# nintendac.net
KiCad netlist of a schematic drawn in EAGLE
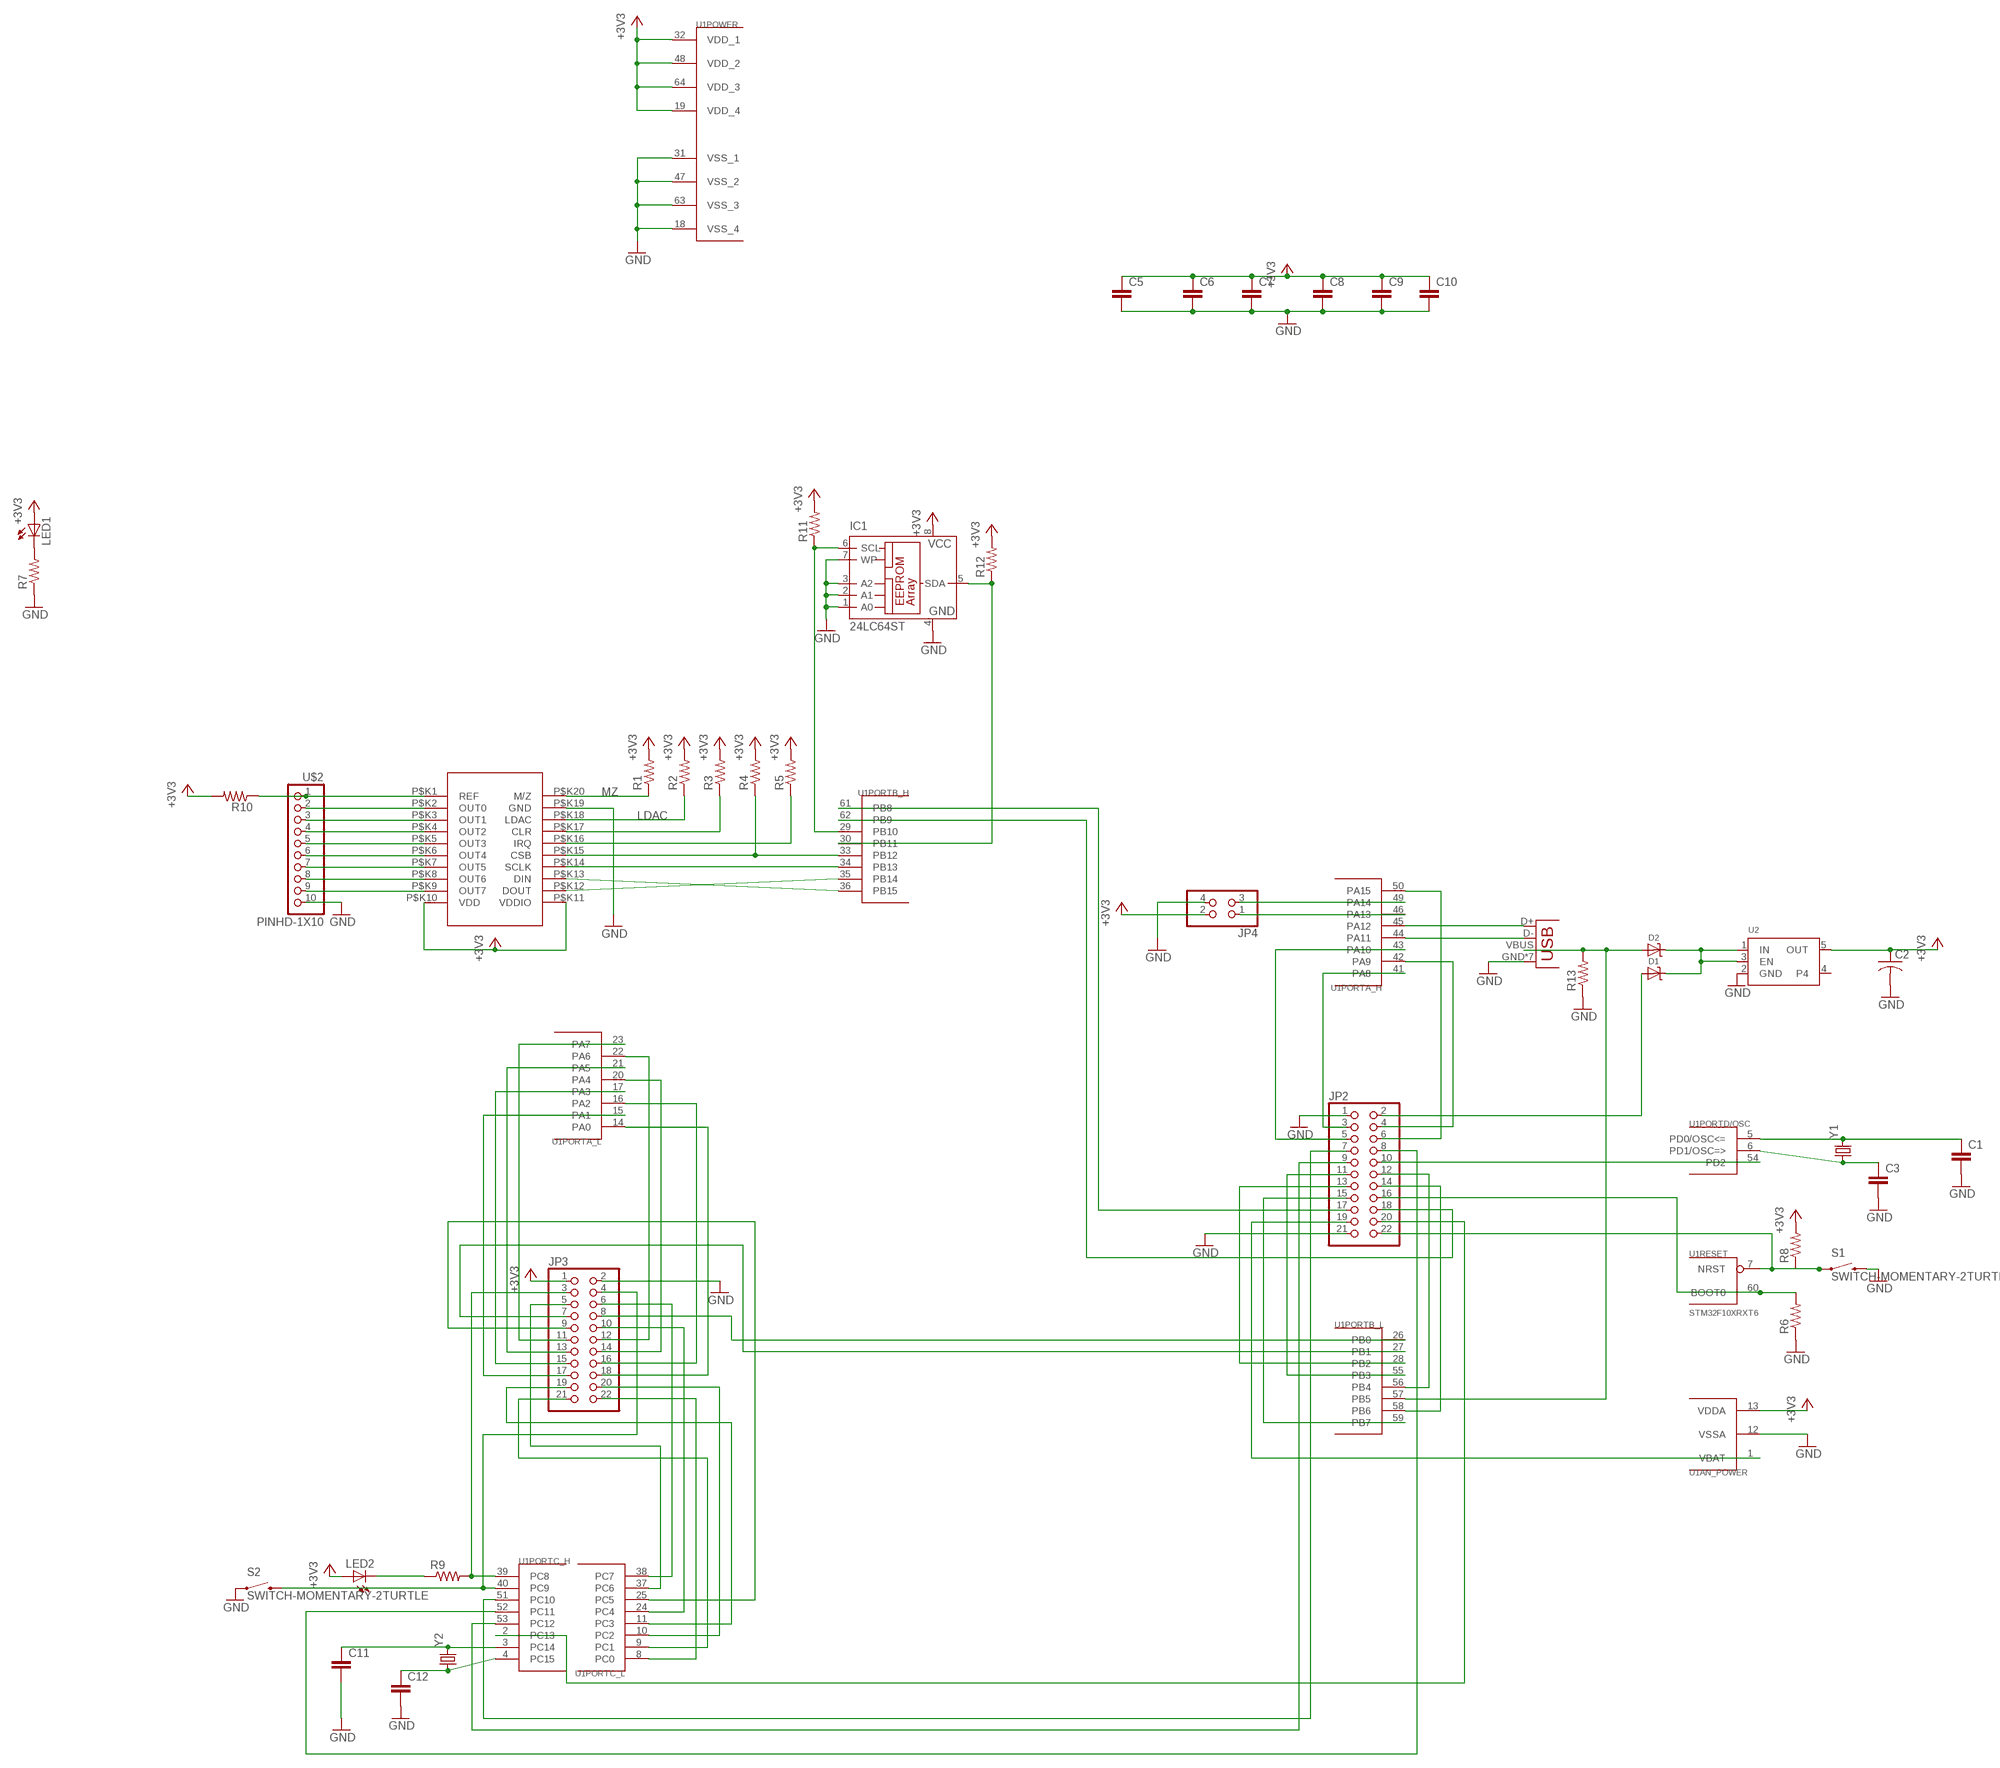
[diagram p0: schematic, sheet 1]

(export (version "E")
  (design (tool "Eeschema 10.0.6"))
  (components
    (comp (ref "C1")
      (value "CAP0805")
      (footprint "eagle-import:0805")
      (libsource (lib "eagle-import") (part "CAP0805"))
    )
    (comp (ref "C2")
      (value "C-USC1210")
      (footprint "eagle-import:C1210")
      (libsource (lib "eagle-import") (part "C-USC1210"))
    )
    (comp (ref "C3")
      (value "CAP0805")
      (footprint "eagle-import:0805")
      (libsource (lib "eagle-import") (part "CAP0805"))
    )
    (comp (ref "C5")
      (value "CAP0805")
      (footprint "eagle-import:0805")
      (libsource (lib "eagle-import") (part "CAP0805"))
    )
    (comp (ref "C6")
      (value "CAP0805")
      (footprint "eagle-import:0805")
      (libsource (lib "eagle-import") (part "CAP0805"))
    )
    (comp (ref "C7")
      (value "CAP0805")
      (footprint "eagle-import:0805")
      (libsource (lib "eagle-import") (part "CAP0805"))
    )
    (comp (ref "C8")
      (value "CAP0805")
      (footprint "eagle-import:0805")
      (libsource (lib "eagle-import") (part "CAP0805"))
    )
    (comp (ref "C9")
      (value "CAP0805")
      (footprint "eagle-import:0805")
      (libsource (lib "eagle-import") (part "CAP0805"))
    )
    (comp (ref "C10")
      (value "CAP0805")
      (footprint "eagle-import:0805")
      (libsource (lib "eagle-import") (part "CAP0805"))
    )
    (comp (ref "C11")
      (value "CAP0805")
      (footprint "eagle-import:0805")
      (libsource (lib "eagle-import") (part "CAP0805"))
    )
    (comp (ref "C12")
      (value "CAP0805")
      (footprint "eagle-import:0805")
      (libsource (lib "eagle-import") (part "CAP0805"))
    )
    (comp (ref "D1")
      (value "DIODE-SCHOTTKYSOD-123")
      (footprint "eagle-import:SOD-123")
      (libsource (lib "eagle-import") (part "DIODE-SCHOTTKYSOD-123"))
    )
    (comp (ref "D2")
      (value "DIODE-SCHOTTKYSOD-123")
      (footprint "eagle-import:SOD-123")
      (libsource (lib "eagle-import") (part "DIODE-SCHOTTKYSOD-123"))
    )
    (comp (ref "IC1")
      (value "24LC64ST")
      (footprint "eagle-import:TSSOP8")
      (fields (field (name "MF") "MICROCHIP") (field (name "MPN") "24LC64X-I/ST"))
      (libsource (lib "eagle-import") (part "24STLC64"))
    )
    (comp (ref "JP2")
      (value "PINHD-2X11")
      (footprint "eagle-import:2X11")
      (libsource (lib "eagle-import") (part "PINHD-2X11"))
    )
    (comp (ref "JP3")
      (value "PINHD-2X11")
      (footprint "eagle-import:2X11")
      (libsource (lib "eagle-import") (part "PINHD-2X11"))
    )
    (comp (ref "JP4")
      (value "PINHD-2X2")
      (footprint "eagle-import:2X02")
      (libsource (lib "eagle-import") (part "PINHD-2X2"))
    )
    (comp (ref "LED1")
      (value "LEDCHIP-LED0805")
      (footprint "eagle-import:CHIP-LED0805")
      (libsource (lib "eagle-import") (part "LEDCHIP-LED0805"))
    )
    (comp (ref "LED2")
      (value "LEDCHIP-LED0805")
      (footprint "eagle-import:CHIP-LED0805")
      (libsource (lib "eagle-import") (part "LEDCHIP-LED0805"))
    )
    (comp (ref "R1")
      (value "RESISTOR0805-RES")
      (footprint "eagle-import:0805")
      (libsource (lib "eagle-import") (part "RESISTOR0805-RES"))
    )
    (comp (ref "R2")
      (value "RESISTOR0805-RES")
      (footprint "eagle-import:0805")
      (libsource (lib "eagle-import") (part "RESISTOR0805-RES"))
    )
    (comp (ref "R3")
      (value "RESISTOR0805-RES")
      (footprint "eagle-import:0805")
      (libsource (lib "eagle-import") (part "RESISTOR0805-RES"))
    )
    (comp (ref "R4")
      (value "RESISTOR0805-RES")
      (footprint "eagle-import:0805")
      (libsource (lib "eagle-import") (part "RESISTOR0805-RES"))
    )
    (comp (ref "R5")
      (value "RESISTOR0805-RES")
      (footprint "eagle-import:0805")
      (libsource (lib "eagle-import") (part "RESISTOR0805-RES"))
    )
    (comp (ref "R6")
      (value "RESISTOR0805-RES")
      (footprint "eagle-import:0805")
      (libsource (lib "eagle-import") (part "RESISTOR0805-RES"))
    )
    (comp (ref "R7")
      (value "RESISTOR0805-RES")
      (footprint "eagle-import:0805")
      (libsource (lib "eagle-import") (part "RESISTOR0805-RES"))
    )
    (comp (ref "R8")
      (value "RESISTOR0805-RES")
      (footprint "eagle-import:0805")
      (libsource (lib "eagle-import") (part "RESISTOR0805-RES"))
    )
    (comp (ref "R9")
      (value "RESISTOR0805-RES")
      (footprint "eagle-import:0805")
      (libsource (lib "eagle-import") (part "RESISTOR0805-RES"))
    )
    (comp (ref "R10")
      (value "RESISTOR0805-RES")
      (footprint "eagle-import:0805")
      (libsource (lib "eagle-import") (part "RESISTOR0805-RES"))
    )
    (comp (ref "R11")
      (value "RESISTOR0805-RES")
      (footprint "eagle-import:0805")
      (libsource (lib "eagle-import") (part "RESISTOR0805-RES"))
    )
    (comp (ref "R12")
      (value "RESISTOR0805-RES")
      (footprint "eagle-import:0805")
      (libsource (lib "eagle-import") (part "RESISTOR0805-RES"))
    )
    (comp (ref "R13")
      (value "RESISTOR0805-RES")
      (footprint "eagle-import:0805")
      (libsource (lib "eagle-import") (part "RESISTOR0805-RES"))
    )
    (comp (ref "S1")
      (value "SWITCH-MOMENTARY-2TURTLE")
      (footprint "eagle-import:KMR2")
      (libsource (lib "eagle-import") (part "SWITCH-MOMENTARY-2TURTLE"))
    )
    (comp (ref "S2")
      (value "SWITCH-MOMENTARY-2TURTLE")
      (footprint "eagle-import:KMR2")
      (libsource (lib "eagle-import") (part "SWITCH-MOMENTARY-2TURTLE"))
    )
    (comp (ref "U$1")
      (value "MAX572X")
      (footprint "eagle-import:TSSOP20")
      (libsource (lib "eagle-import") (part "MAX572X"))
    )
    (comp (ref "U$2")
      (value "PINHD-1X10")
      (footprint "eagle-import:1X10-BIG")
      (libsource (lib "eagle-import") (part "PINHD-1X10"))
    )
    (comp (ref "U1")
      (value "STM32F10XRXT6")
      (footprint "eagle-import:TQFP64")
      (libsource (lib "eagle-import") (part "STM32F10XRXT6"))
    )
    (comp (ref "U2")
      (value "VREG_SOT23-5")
      (footprint "eagle-import:SOT23-5")
      (libsource (lib "eagle-import") (part "VREG_SOT23-5"))
    )
    (comp (ref "X1")
      (value "USB-MICROB")
      (footprint "eagle-import:USB-MICROB")
      (libsource (lib "eagle-import") (part "USB-MICROB"))
    )
    (comp (ref "Y1")
      (value "CRYSTALHC49US")
      (footprint "eagle-import:HC49US")
      (libsource (lib "eagle-import") (part "CRYSTALHC49US"))
    )
    (comp (ref "Y2")
      (value "CRYSTALTC26H_EZ")
      (footprint "eagle-import:TC26HEZ")
      (libsource (lib "eagle-import") (part "CRYSTALTC26H_EZ"))
    )
  )
  (nets
    (net (code "1") (name "+3V3") (class "Default")
      (node (ref "C10") (pin "1") (pinfunction "1_1") (pintype "passive"))
      (node (ref "C2") (pin "1") (pinfunction "1_1") (pintype "passive"))
      (node (ref "C5") (pin "1") (pinfunction "1_1") (pintype "passive"))
      (node (ref "C6") (pin "1") (pinfunction "1_1") (pintype "passive"))
      (node (ref "C7") (pin "1") (pinfunction "1_1") (pintype "passive"))
      (node (ref "C8") (pin "1") (pinfunction "1_1") (pintype "passive"))
      (node (ref "C9") (pin "1") (pinfunction "1_1") (pintype "passive"))
      (node (ref "IC1") (pin "8") (pinfunction "VCC_8") (pintype "power_in"))
      (node (ref "JP3") (pin "1") (pinfunction "1_1") (pintype "passive"))
      (node (ref "JP4") (pin "2") (pinfunction "2_2") (pintype "passive"))
      (node (ref "LED1") (pin "A") (pinfunction "A_A") (pintype "passive"))
      (node (ref "LED2") (pin "A") (pinfunction "A_A") (pintype "passive"))
      (node (ref "R1") (pin "2") (pinfunction "2_2") (pintype "passive"))
      (node (ref "R10") (pin "2") (pinfunction "2_2") (pintype "passive"))
      (node (ref "R11") (pin "2") (pinfunction "2_2") (pintype "passive"))
      (node (ref "R12") (pin "2") (pinfunction "2_2") (pintype "passive"))
      (node (ref "R2") (pin "2") (pinfunction "2_2") (pintype "passive"))
      (node (ref "R3") (pin "2") (pinfunction "2_2") (pintype "passive"))
      (node (ref "R4") (pin "2") (pinfunction "2_2") (pintype "passive"))
      (node (ref "R5") (pin "2") (pinfunction "2_2") (pintype "passive"))
      (node (ref "R8") (pin "2") (pinfunction "2_2") (pintype "passive"))
      (node (ref "U$1") (pin "P$K10") (pinfunction "VDD_P$K10") (pintype "bidirectional"))
      (node (ref "U$1") (pin "P$K11") (pinfunction "VDDIO_P$K11") (pintype "bidirectional"))
      (node (ref "U1") (pin "13") (pinfunction "VDDA_13") (pintype "power_in"))
      (node (ref "U1") (pin "19") (pinfunction "VDD_4_19") (pintype "power_in"))
      (node (ref "U1") (pin "32") (pinfunction "VDD_1_32") (pintype "power_in"))
      (node (ref "U1") (pin "48") (pinfunction "VDD_2_48") (pintype "power_in"))
      (node (ref "U1") (pin "64") (pinfunction "VDD_3_64") (pintype "power_in"))
      (node (ref "U2") (pin "5") (pinfunction "OUT_5") (pintype "power_in"))
    )
    (net (code "2") (name "/LDAC") (class "Default")
      (node (ref "R2") (pin "1") (pinfunction "1_1") (pintype "passive"))
      (node (ref "U$1") (pin "P$K18") (pinfunction "LDAC_P$K18") (pintype "bidirectional"))
    )
    (net (code "3") (name "/MZ") (class "Default")
      (node (ref "R1") (pin "1") (pinfunction "1_1") (pintype "passive"))
      (node (ref "U$1") (pin "P$K20") (pinfunction "M/Z_P$K20") (pintype "bidirectional"))
    )
    (net (code "4") (name "GND") (class "Default")
      (node (ref "C1") (pin "2") (pinfunction "2_2") (pintype "passive"))
      (node (ref "C10") (pin "2") (pinfunction "2_2") (pintype "passive"))
      (node (ref "C11") (pin "2") (pinfunction "2_2") (pintype "passive"))
      (node (ref "C12") (pin "2") (pinfunction "2_2") (pintype "passive"))
      (node (ref "C2") (pin "2") (pinfunction "2_2") (pintype "passive"))
      (node (ref "C3") (pin "2") (pinfunction "2_2") (pintype "passive"))
      (node (ref "C5") (pin "2") (pinfunction "2_2") (pintype "passive"))
      (node (ref "C6") (pin "2") (pinfunction "2_2") (pintype "passive"))
      (node (ref "C7") (pin "2") (pinfunction "2_2") (pintype "passive"))
      (node (ref "C8") (pin "2") (pinfunction "2_2") (pintype "passive"))
      (node (ref "C9") (pin "2") (pinfunction "2_2") (pintype "passive"))
      (node (ref "IC1") (pin "1") (pinfunction "A0_1") (pintype "input"))
      (node (ref "IC1") (pin "2") (pinfunction "A1_2") (pintype "input"))
      (node (ref "IC1") (pin "3") (pinfunction "A2_3") (pintype "input"))
      (node (ref "IC1") (pin "4") (pinfunction "GND_4") (pintype "power_in"))
      (node (ref "IC1") (pin "7") (pinfunction "WP_7") (pintype "input"))
      (node (ref "JP2") (pin "1") (pinfunction "1_1") (pintype "passive"))
      (node (ref "JP2") (pin "21") (pinfunction "21_21") (pintype "passive"))
      (node (ref "JP3") (pin "2") (pinfunction "2_2") (pintype "passive"))
      (node (ref "JP4") (pin "4") (pinfunction "4_4") (pintype "passive"))
      (node (ref "R13") (pin "1") (pinfunction "1_1") (pintype "passive"))
      (node (ref "R6") (pin "1") (pinfunction "1_1") (pintype "passive"))
      (node (ref "R7") (pin "1") (pinfunction "1_1") (pintype "passive"))
      (node (ref "S1") (pin "3") (pinfunction "2_3") (pintype "passive"))
      (node (ref "S2") (pin "1") (pinfunction "1_1") (pintype "passive"))
      (node (ref "U$1") (pin "P$K19") (pinfunction "GND_P$K19") (pintype "bidirectional"))
      (node (ref "U$2") (pin "10") (pinfunction "10_10") (pintype "passive"))
      (node (ref "U1") (pin "12") (pinfunction "VSSA_12") (pintype "power_in"))
      (node (ref "U1") (pin "18") (pinfunction "VSS_4_18") (pintype "power_in"))
      (node (ref "U1") (pin "31") (pinfunction "VSS_1_31") (pintype "power_in"))
      (node (ref "U1") (pin "47") (pinfunction "VSS_2_47") (pintype "power_in"))
      (node (ref "U1") (pin "63") (pinfunction "VSS_3_63") (pintype "power_in"))
      (node (ref "U2") (pin "2") (pinfunction "GND_2") (pintype "power_in"))
      (node (ref "X1") (pin "GND") (pinfunction "GND_GND") (pintype "bidirectional"))
      (node (ref "X1") (pin "P1") (pinfunction "GND_P1") (pintype "bidirectional"))
      (node (ref "X1") (pin "P2") (pinfunction "GND_P2") (pintype "bidirectional"))
      (node (ref "X1") (pin "P3") (pinfunction "GND_P3") (pintype "bidirectional"))
      (node (ref "X1") (pin "P4") (pinfunction "GND_P4") (pintype "bidirectional"))
      (node (ref "X1") (pin "P5") (pinfunction "GND_P5") (pintype "bidirectional"))
      (node (ref "X1") (pin "P6") (pinfunction "GND_P6") (pintype "bidirectional"))
    )
    (net (code "5") (name "Net-(D1-PadA)") (class "Default")
      (node (ref "D1") (pin "A") (pinfunction "A_A") (pintype "passive"))
      (node (ref "JP2") (pin "2") (pinfunction "2_2") (pintype "passive"))
    )
    (net (code "6") (name "Net-(IC1-SCL)") (class "Default")
      (node (ref "IC1") (pin "6") (pinfunction "SCL_6") (pintype "input"))
      (node (ref "R11") (pin "1") (pinfunction "1_1") (pintype "passive"))
      (node (ref "U1") (pin "29") (pinfunction "PB10_29") (pintype "bidirectional"))
    )
    (net (code "7") (name "Net-(IC1-SDA)") (class "Default")
      (node (ref "IC1") (pin "5") (pinfunction "SDA_5") (pintype "bidirectional"))
      (node (ref "R12") (pin "1") (pinfunction "1_1") (pintype "passive"))
      (node (ref "U1") (pin "30") (pinfunction "PB11_30") (pintype "bidirectional"))
    )
    (net (code "8") (name "Net-(LED1-PadC)") (class "Default")
      (node (ref "LED1") (pin "C") (pinfunction "C_C") (pintype "passive"))
      (node (ref "R7") (pin "2") (pinfunction "2_2") (pintype "passive"))
    )
    (net (code "9") (name "Net-(LED2-PadC)") (class "Default")
      (node (ref "LED2") (pin "C") (pinfunction "C_C") (pintype "passive"))
      (node (ref "R9") (pin "1") (pinfunction "1_1") (pintype "passive"))
    )
    (net (code "10") (name "Net-(S2-2)") (class "Default")
      (node (ref "JP3") (pin "4") (pinfunction "4_4") (pintype "passive"))
      (node (ref "S2") (pin "3") (pinfunction "2_3") (pintype "passive"))
      (node (ref "U1") (pin "40") (pinfunction "PC9_40") (pintype "bidirectional"))
    )
    (net (code "11") (name "Net-(U$1-CLR)") (class "Default")
      (node (ref "R3") (pin "1") (pinfunction "1_1") (pintype "passive"))
      (node (ref "U$1") (pin "P$K17") (pinfunction "CLR_P$K17") (pintype "bidirectional"))
    )
    (net (code "12") (name "Net-(U$1-CSB)") (class "Default")
      (node (ref "R4") (pin "1") (pinfunction "1_1") (pintype "passive"))
      (node (ref "U$1") (pin "P$K15") (pinfunction "CSB_P$K15") (pintype "bidirectional"))
      (node (ref "U1") (pin "33") (pinfunction "PB12_33") (pintype "bidirectional"))
    )
    (net (code "13") (name "Net-(U$1-DIN)") (class "Default")
      (node (ref "U$1") (pin "P$K13") (pinfunction "DIN_P$K13") (pintype "bidirectional"))
      (node (ref "U1") (pin "36") (pinfunction "PB15_36") (pintype "bidirectional"))
    )
    (net (code "14") (name "Net-(U$1-DOUT)") (class "Default")
      (node (ref "U$1") (pin "P$K12") (pinfunction "DOUT_P$K12") (pintype "bidirectional"))
      (node (ref "U1") (pin "35") (pinfunction "PB14_35") (pintype "bidirectional"))
    )
    (net (code "15") (name "Net-(U$1-IRQ)") (class "Default")
      (node (ref "R5") (pin "1") (pinfunction "1_1") (pintype "passive"))
      (node (ref "U$1") (pin "P$K16") (pinfunction "IRQ_P$K16") (pintype "bidirectional"))
    )
    (net (code "16") (name "Net-(U$1-OUT0)") (class "Default")
      (node (ref "U$1") (pin "P$K2") (pinfunction "OUT0_P$K2") (pintype "bidirectional"))
      (node (ref "U$2") (pin "2") (pinfunction "2_2") (pintype "passive"))
    )
    (net (code "17") (name "Net-(U$1-OUT1)") (class "Default")
      (node (ref "U$1") (pin "P$K3") (pinfunction "OUT1_P$K3") (pintype "bidirectional"))
      (node (ref "U$2") (pin "3") (pinfunction "3_3") (pintype "passive"))
    )
    (net (code "18") (name "Net-(U$1-OUT2)") (class "Default")
      (node (ref "U$1") (pin "P$K4") (pinfunction "OUT2_P$K4") (pintype "bidirectional"))
      (node (ref "U$2") (pin "4") (pinfunction "4_4") (pintype "passive"))
    )
    (net (code "19") (name "Net-(U$1-OUT3)") (class "Default")
      (node (ref "U$1") (pin "P$K5") (pinfunction "OUT3_P$K5") (pintype "bidirectional"))
      (node (ref "U$2") (pin "5") (pinfunction "5_5") (pintype "passive"))
    )
    (net (code "20") (name "Net-(U$1-OUT4)") (class "Default")
      (node (ref "U$1") (pin "P$K6") (pinfunction "OUT4_P$K6") (pintype "bidirectional"))
      (node (ref "U$2") (pin "6") (pinfunction "6_6") (pintype "passive"))
    )
    (net (code "21") (name "Net-(U$1-OUT5)") (class "Default")
      (node (ref "U$1") (pin "P$K7") (pinfunction "OUT5_P$K7") (pintype "bidirectional"))
      (node (ref "U$2") (pin "7") (pinfunction "7_7") (pintype "passive"))
    )
    (net (code "22") (name "Net-(U$1-OUT6)") (class "Default")
      (node (ref "U$1") (pin "P$K8") (pinfunction "OUT6_P$K8") (pintype "bidirectional"))
      (node (ref "U$2") (pin "8") (pinfunction "8_8") (pintype "passive"))
    )
    (net (code "23") (name "Net-(U$1-OUT7)") (class "Default")
      (node (ref "U$1") (pin "P$K9") (pinfunction "OUT7_P$K9") (pintype "bidirectional"))
      (node (ref "U$2") (pin "9") (pinfunction "9_9") (pintype "passive"))
    )
    (net (code "24") (name "Net-(U$1-REF)") (class "Default")
      (node (ref "R10") (pin "1") (pinfunction "1_1") (pintype "passive"))
      (node (ref "U$1") (pin "P$K1") (pinfunction "REF_P$K1") (pintype "bidirectional"))
      (node (ref "U$2") (pin "1") (pinfunction "1_1") (pintype "passive"))
    )
    (net (code "25") (name "Net-(U$1-SCLK)") (class "Default")
      (node (ref "U$1") (pin "P$K14") (pinfunction "SCLK_P$K14") (pintype "bidirectional"))
      (node (ref "U1") (pin "34") (pinfunction "PB13_34") (pintype "bidirectional"))
    )
    (net (code "26") (name "Net-(U1A-VBAT)") (class "Default")
      (node (ref "JP2") (pin "19") (pinfunction "19_19") (pintype "passive"))
      (node (ref "U1") (pin "1") (pinfunction "VBAT_1") (pintype "power_in"))
    )
    (net (code "27") (name "Net-(U1B-PA8)") (class "Default")
      (node (ref "JP2") (pin "3") (pinfunction "3_3") (pintype "passive"))
      (node (ref "U1") (pin "41") (pinfunction "PA8_41") (pintype "bidirectional"))
    )
    (net (code "28") (name "Net-(U1B-PA9)") (class "Default")
      (node (ref "JP2") (pin "4") (pinfunction "4_4") (pintype "passive"))
      (node (ref "U1") (pin "42") (pinfunction "PA9_42") (pintype "bidirectional"))
    )
    (net (code "29") (name "Net-(U1B-PA10)") (class "Default")
      (node (ref "JP2") (pin "5") (pinfunction "5_5") (pintype "passive"))
      (node (ref "U1") (pin "43") (pinfunction "PA10_43") (pintype "bidirectional"))
    )
    (net (code "30") (name "Net-(U1B-PA11)") (class "Default")
      (node (ref "U1") (pin "44") (pinfunction "PA11_44") (pintype "bidirectional"))
      (node (ref "X1") (pin "D-") (pinfunction "D-_D-") (pintype "bidirectional"))
    )
    (net (code "31") (name "Net-(U1B-PA12)") (class "Default")
      (node (ref "U1") (pin "45") (pinfunction "PA12_45") (pintype "bidirectional"))
      (node (ref "X1") (pin "D+") (pinfunction "D+_D+") (pintype "bidirectional"))
    )
    (net (code "32") (name "Net-(U1B-PA13)") (class "Default")
      (node (ref "JP4") (pin "1") (pinfunction "1_1") (pintype "passive"))
      (node (ref "U1") (pin "46") (pinfunction "PA13_46") (pintype "bidirectional"))
    )
    (net (code "33") (name "Net-(U1B-PA14)") (class "Default")
      (node (ref "JP4") (pin "3") (pinfunction "3_3") (pintype "passive"))
      (node (ref "U1") (pin "49") (pinfunction "PA14_49") (pintype "bidirectional"))
    )
    (net (code "34") (name "Net-(U1B-PA15)") (class "Default")
      (node (ref "JP2") (pin "6") (pinfunction "6_6") (pintype "passive"))
      (node (ref "U1") (pin "50") (pinfunction "PA15_50") (pintype "bidirectional"))
    )
    (net (code "35") (name "Net-(U1C-PA0)") (class "Default")
      (node (ref "JP3") (pin "18") (pinfunction "18_18") (pintype "passive"))
      (node (ref "U1") (pin "14") (pinfunction "PA0_14") (pintype "bidirectional"))
    )
    (net (code "36") (name "Net-(U1C-PA1)") (class "Default")
      (node (ref "JP3") (pin "17") (pinfunction "17_17") (pintype "passive"))
      (node (ref "U1") (pin "15") (pinfunction "PA1_15") (pintype "bidirectional"))
    )
    (net (code "37") (name "Net-(U1C-PA2)") (class "Default")
      (node (ref "JP3") (pin "16") (pinfunction "16_16") (pintype "passive"))
      (node (ref "U1") (pin "16") (pinfunction "PA2_16") (pintype "bidirectional"))
    )
    (net (code "38") (name "Net-(U1C-PA3)") (class "Default")
      (node (ref "JP3") (pin "15") (pinfunction "15_15") (pintype "passive"))
      (node (ref "U1") (pin "17") (pinfunction "PA3_17") (pintype "bidirectional"))
    )
    (net (code "39") (name "Net-(U1C-PA4)") (class "Default")
      (node (ref "JP3") (pin "14") (pinfunction "14_14") (pintype "passive"))
      (node (ref "U1") (pin "20") (pinfunction "PA4_20") (pintype "bidirectional"))
    )
    (net (code "40") (name "Net-(U1C-PA5)") (class "Default")
      (node (ref "JP3") (pin "13") (pinfunction "13_13") (pintype "passive"))
      (node (ref "U1") (pin "21") (pinfunction "PA5_21") (pintype "bidirectional"))
    )
    (net (code "41") (name "Net-(U1C-PA6)") (class "Default")
      (node (ref "JP3") (pin "12") (pinfunction "12_12") (pintype "passive"))
      (node (ref "U1") (pin "22") (pinfunction "PA6_22") (pintype "bidirectional"))
    )
    (net (code "42") (name "Net-(U1C-PA7)") (class "Default")
      (node (ref "JP3") (pin "11") (pinfunction "11_11") (pintype "passive"))
      (node (ref "U1") (pin "23") (pinfunction "PA7_23") (pintype "bidirectional"))
    )
    (net (code "43") (name "Net-(U1D-PB8)") (class "Default")
      (node (ref "JP2") (pin "17") (pinfunction "17_17") (pintype "passive"))
      (node (ref "U1") (pin "61") (pinfunction "PB8_61") (pintype "bidirectional"))
    )
    (net (code "44") (name "Net-(U1D-PB9)") (class "Default")
      (node (ref "JP2") (pin "18") (pinfunction "18_18") (pintype "passive"))
      (node (ref "U1") (pin "62") (pinfunction "PB9_62") (pintype "bidirectional"))
    )
    (net (code "45") (name "Net-(U1E-PB0)") (class "Default")
      (node (ref "JP3") (pin "8") (pinfunction "8_8") (pintype "passive"))
      (node (ref "U1") (pin "26") (pinfunction "PB0_26") (pintype "bidirectional"))
    )
    (net (code "46") (name "Net-(U1E-PB1)") (class "Default")
      (node (ref "JP3") (pin "7") (pinfunction "7_7") (pintype "passive"))
      (node (ref "U1") (pin "27") (pinfunction "PB1_27") (pintype "bidirectional"))
    )
    (net (code "47") (name "Net-(U1E-PB2)") (class "Default")
      (node (ref "JP2") (pin "13") (pinfunction "13_13") (pintype "passive"))
      (node (ref "U1") (pin "28") (pinfunction "PB2_28") (pintype "bidirectional"))
    )
    (net (code "48") (name "Net-(U1E-PB3)") (class "Default")
      (node (ref "JP2") (pin "11") (pinfunction "11_11") (pintype "passive"))
      (node (ref "U1") (pin "55") (pinfunction "PB3_55") (pintype "bidirectional"))
    )
    (net (code "49") (name "Net-(U1E-PB4)") (class "Default")
      (node (ref "JP2") (pin "12") (pinfunction "12_12") (pintype "passive"))
      (node (ref "U1") (pin "56") (pinfunction "PB4_56") (pintype "bidirectional"))
    )
    (net (code "50") (name "Net-(U1E-PB5)") (class "Default")
      (node (ref "D2") (pin "A") (pinfunction "A_A") (pintype "passive"))
      (node (ref "R13") (pin "2") (pinfunction "2_2") (pintype "passive"))
      (node (ref "U1") (pin "57") (pinfunction "PB5_57") (pintype "bidirectional"))
      (node (ref "X1") (pin "VBUS") (pinfunction "VBUS_VBUS") (pintype "bidirectional"))
    )
    (net (code "51") (name "Net-(U1E-PB6)") (class "Default")
      (node (ref "JP2") (pin "14") (pinfunction "14_14") (pintype "passive"))
      (node (ref "U1") (pin "58") (pinfunction "PB6_58") (pintype "bidirectional"))
    )
    (net (code "52") (name "Net-(U1E-PB7)") (class "Default")
      (node (ref "JP2") (pin "15") (pinfunction "15_15") (pintype "passive"))
      (node (ref "U1") (pin "59") (pinfunction "PB7_59") (pintype "bidirectional"))
    )
    (net (code "53") (name "Net-(U1F-PC8)") (class "Default")
      (node (ref "JP3") (pin "3") (pinfunction "3_3") (pintype "passive"))
      (node (ref "R9") (pin "2") (pinfunction "2_2") (pintype "passive"))
      (node (ref "U1") (pin "39") (pinfunction "PC8_39") (pintype "bidirectional"))
    )
    (net (code "54") (name "Net-(U1F-PC10)") (class "Default")
      (node (ref "JP2") (pin "7") (pinfunction "7_7") (pintype "passive"))
      (node (ref "U1") (pin "51") (pinfunction "PC10_51") (pintype "bidirectional"))
    )
    (net (code "55") (name "Net-(U1F-PC11)") (class "Default")
      (node (ref "JP2") (pin "8") (pinfunction "8_8") (pintype "passive"))
      (node (ref "U1") (pin "52") (pinfunction "PC11_52") (pintype "bidirectional"))
    )
    (net (code "56") (name "Net-(U1F-PC12)") (class "Default")
      (node (ref "JP2") (pin "9") (pinfunction "9_9") (pintype "passive"))
      (node (ref "U1") (pin "53") (pinfunction "PC12_53") (pintype "bidirectional"))
    )
    (net (code "57") (name "Net-(U1F-PC13)") (class "Default")
      (node (ref "JP2") (pin "20") (pinfunction "20_20") (pintype "passive"))
      (node (ref "U1") (pin "2") (pinfunction "PC13_2") (pintype "bidirectional"))
    )
    (net (code "58") (name "Net-(U1F-PC14)") (class "Default")
      (node (ref "C11") (pin "1") (pinfunction "1_1") (pintype "passive"))
      (node (ref "U1") (pin "3") (pinfunction "PC14_3") (pintype "bidirectional"))
      (node (ref "Y2") (pin "2") (pinfunction "2_2") (pintype "passive"))
    )
    (net (code "59") (name "Net-(U1F-PC15)") (class "Default")
      (node (ref "C12") (pin "1") (pinfunction "1_1") (pintype "passive"))
      (node (ref "U1") (pin "4") (pinfunction "PC15_4") (pintype "bidirectional"))
      (node (ref "Y2") (pin "1") (pinfunction "1_1") (pintype "passive"))
    )
    (net (code "60") (name "Net-(U1G-PC0)") (class "Default")
      (node (ref "JP3") (pin "22") (pinfunction "22_22") (pintype "passive"))
      (node (ref "U1") (pin "8") (pinfunction "PC0_8") (pintype "bidirectional"))
    )
    (net (code "61") (name "Net-(U1G-PC1)") (class "Default")
      (node (ref "JP3") (pin "21") (pinfunction "21_21") (pintype "passive"))
      (node (ref "U1") (pin "9") (pinfunction "PC1_9") (pintype "bidirectional"))
    )
    (net (code "62") (name "Net-(U1G-PC2)") (class "Default")
      (node (ref "JP3") (pin "20") (pinfunction "20_20") (pintype "passive"))
      (node (ref "U1") (pin "10") (pinfunction "PC2_10") (pintype "bidirectional"))
    )
    (net (code "63") (name "Net-(U1G-PC3)") (class "Default")
      (node (ref "JP3") (pin "19") (pinfunction "19_19") (pintype "passive"))
      (node (ref "U1") (pin "11") (pinfunction "PC3_11") (pintype "bidirectional"))
    )
    (net (code "64") (name "Net-(U1G-PC4)") (class "Default")
      (node (ref "JP3") (pin "10") (pinfunction "10_10") (pintype "passive"))
      (node (ref "U1") (pin "24") (pinfunction "PC4_24") (pintype "bidirectional"))
    )
    (net (code "65") (name "Net-(U1G-PC5)") (class "Default")
      (node (ref "JP3") (pin "9") (pinfunction "9_9") (pintype "passive"))
      (node (ref "U1") (pin "25") (pinfunction "PC5_25") (pintype "bidirectional"))
    )
    (net (code "66") (name "Net-(U1G-PC6)") (class "Default")
      (node (ref "JP3") (pin "5") (pinfunction "5_5") (pintype "passive"))
      (node (ref "U1") (pin "37") (pinfunction "PC6_37") (pintype "bidirectional"))
    )
    (net (code "67") (name "Net-(U1G-PC7)") (class "Default")
      (node (ref "JP3") (pin "6") (pinfunction "6_6") (pintype "passive"))
      (node (ref "U1") (pin "38") (pinfunction "PC7_38") (pintype "bidirectional"))
    )
    (net (code "68") (name "Net-(U1H-PD0{slash}OSC<=)") (class "Default")
      (node (ref "C1") (pin "1") (pinfunction "1_1") (pintype "passive"))
      (node (ref "U1") (pin "5") (pinfunction "PD0/OSC<=_5") (pintype "bidirectional"))
      (node (ref "Y1") (pin "2") (pinfunction "2_2") (pintype "passive"))
    )
    (net (code "69") (name "Net-(U1H-PD1{slash}OSC=>)") (class "Default")
      (node (ref "C3") (pin "1") (pinfunction "1_1") (pintype "passive"))
      (node (ref "U1") (pin "6") (pinfunction "PD1/OSC=>_6") (pintype "bidirectional"))
      (node (ref "Y1") (pin "1") (pinfunction "1_1") (pintype "passive"))
    )
    (net (code "70") (name "Net-(U1H-PD2)") (class "Default")
      (node (ref "JP2") (pin "10") (pinfunction "10_10") (pintype "passive"))
      (node (ref "U1") (pin "54") (pinfunction "PD2_54") (pintype "bidirectional"))
    )
    (net (code "71") (name "Net-(U1J-BOOT0)") (class "Default")
      (node (ref "JP2") (pin "16") (pinfunction "16_16") (pintype "passive"))
      (node (ref "R6") (pin "2") (pinfunction "2_2") (pintype "passive"))
      (node (ref "U1") (pin "60") (pinfunction "BOOT0_60") (pintype "input"))
    )
    (net (code "72") (name "Net-(U1J-NRST)") (class "Default")
      (node (ref "JP2") (pin "22") (pinfunction "22_22") (pintype "passive"))
      (node (ref "R8") (pin "1") (pinfunction "1_1") (pintype "passive"))
      (node (ref "S1") (pin "1") (pinfunction "1_1") (pintype "passive"))
      (node (ref "U1") (pin "7") (pinfunction "NRST_7") (pintype "input"))
    )
    (net (code "73") (name "Net-(U2-EN)") (class "Default")
      (node (ref "D1") (pin "C") (pinfunction "C_C") (pintype "passive"))
      (node (ref "D2") (pin "C") (pinfunction "C_C") (pintype "passive"))
      (node (ref "U2") (pin "1") (pinfunction "IN_1") (pintype "power_in"))
      (node (ref "U2") (pin "3") (pinfunction "EN_3") (pintype "input"))
    )
    (net (code "74") (name "unconnected-(U2-P4-Pad4)") (class "Default")
      (node (ref "U2") (pin "4") (pinfunction "P4_4") (pintype "bidirectional"))
    )
  )
)
